# power.net
KiCad netlist of a schematic drawn in Altium Designer
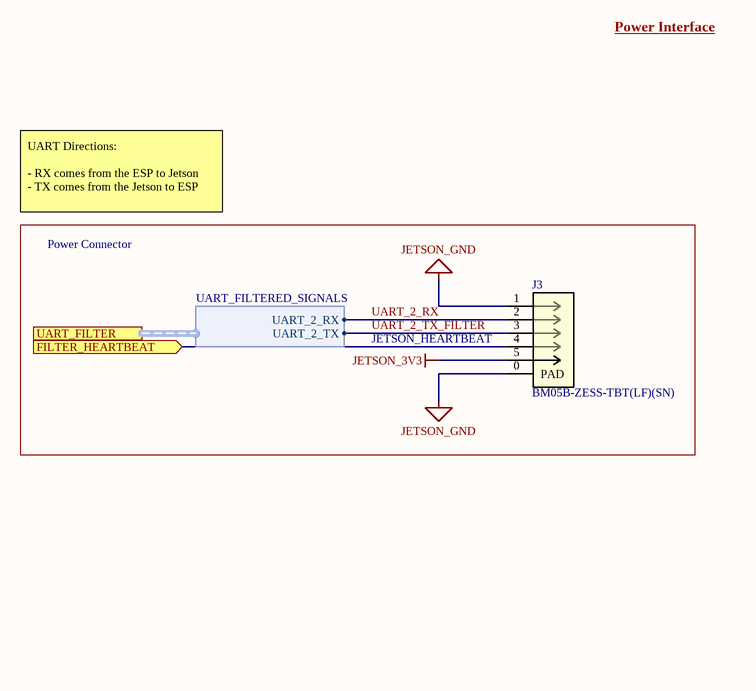
[diagram p0: power.SchDoc]

(export (version "E")
  (design (tool "Eeschema 10.0.6"))
  (components
    (comp (ref "J3")
      (value "BM05B-ZESS-TBT(LF)(SN)")
      (footprint "JST ZE SMT 5POS")
      (description "CONN HEADER VERT SMD 5POS ZE")
      (fields (field (name "PART NUMBER") "CN 5POS JST ZE SMT"))
      (libsource (lib "Connector_Library") (part "CN 5POS JST ZE SMT"))
    )
  )
  (nets
    (net (code "2") (name "/FILTER_HEARTBEAT") (class "Default")
      (node (ref "J3") (pin "4") (pinfunction "4_4") (pintype "passive"))
    )
    (net (code "3") (name "/UART_2_RX") (class "Default")
      (node (ref "J3") (pin "2") (pinfunction "2_2") (pintype "passive"))
    )
    (net (code "4") (name "/UART_2_TX_FILTER") (class "Default")
      (node (ref "J3") (pin "3") (pinfunction "3_3") (pintype "passive"))
    )
    (net (code "6") (name "JETSON_3V3") (class "Default")
      (node (ref "J3") (pin "5") (pinfunction "5_5") (pintype "passive"))
    )
    (net (code "7") (name "JETSON_GND") (class "Default")
      (node (ref "J3") (pin "0") (pinfunction "PAD_0") (pintype "passive"))
      (node (ref "J3") (pin "1") (pinfunction "1_1") (pintype "passive"))
    )
  )
)
